# Atmel328p_SlideOver.net
KiCad netlist of a schematic drawn in EAGLE
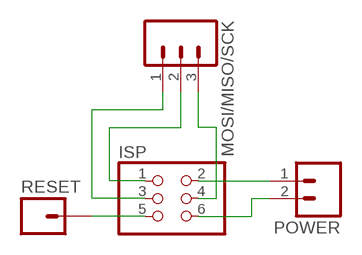
[diagram p0: schematic, sheet 1]

(export (version "E")
  (design (tool "Eeschema 10.0.6"))
  (components
    (comp (ref "ISP")
      (value "PINHD-2X3")
      (footprint "eagle-import:2X03")
      (libsource (lib "eagle-import") (part "PINHD-2X3"))
    )
    (comp (ref "MOSI/MISO/SCK")
      (value "M03PTH")
      (footprint "eagle-import:1X03")
      (libsource (lib "eagle-import") (part "M03PTH"))
    )
    (comp (ref "POWER")
      (value "M02PTH")
      (footprint "eagle-import:1X02")
      (libsource (lib "eagle-import") (part "M02PTH"))
    )
    (comp (ref "RESET")
      (value "M01PTH")
      (footprint "eagle-import:1X01")
      (libsource (lib "eagle-import") (part "M01PTH"))
    )
  )
  (nets
    (net (code "1") (name "Net-(ISP-Pad1)") (class "Default")
      (node (ref "ISP") (pin "1") (pinfunction "1_1") (pintype "passive"))
      (node (ref "MOSI/MISO/SCK") (pin "2") (pinfunction "2_2") (pintype "passive"))
    )
    (net (code "2") (name "Net-(ISP-Pad2)") (class "Default")
      (node (ref "ISP") (pin "2") (pinfunction "2_2") (pintype "passive"))
      (node (ref "POWER") (pin "1") (pinfunction "1_1") (pintype "passive"))
    )
    (net (code "3") (name "Net-(ISP-Pad3)") (class "Default")
      (node (ref "ISP") (pin "3") (pinfunction "3_3") (pintype "passive"))
      (node (ref "MOSI/MISO/SCK") (pin "1") (pinfunction "1_1") (pintype "passive"))
    )
    (net (code "4") (name "Net-(ISP-Pad4)") (class "Default")
      (node (ref "ISP") (pin "4") (pinfunction "4_4") (pintype "passive"))
      (node (ref "MOSI/MISO/SCK") (pin "3") (pinfunction "3_3") (pintype "passive"))
    )
    (net (code "5") (name "Net-(ISP-Pad5)") (class "Default")
      (node (ref "ISP") (pin "5") (pinfunction "5_5") (pintype "passive"))
      (node (ref "RESET") (pin "1") (pinfunction "1_1") (pintype "passive"))
    )
    (net (code "6") (name "Net-(ISP-Pad6)") (class "Default")
      (node (ref "ISP") (pin "6") (pinfunction "6_6") (pintype "passive"))
      (node (ref "POWER") (pin "2") (pinfunction "2_2") (pintype "passive"))
    )
  )
)
